# Chime_PCB.net
KiCad netlist of a schematic drawn in EAGLE
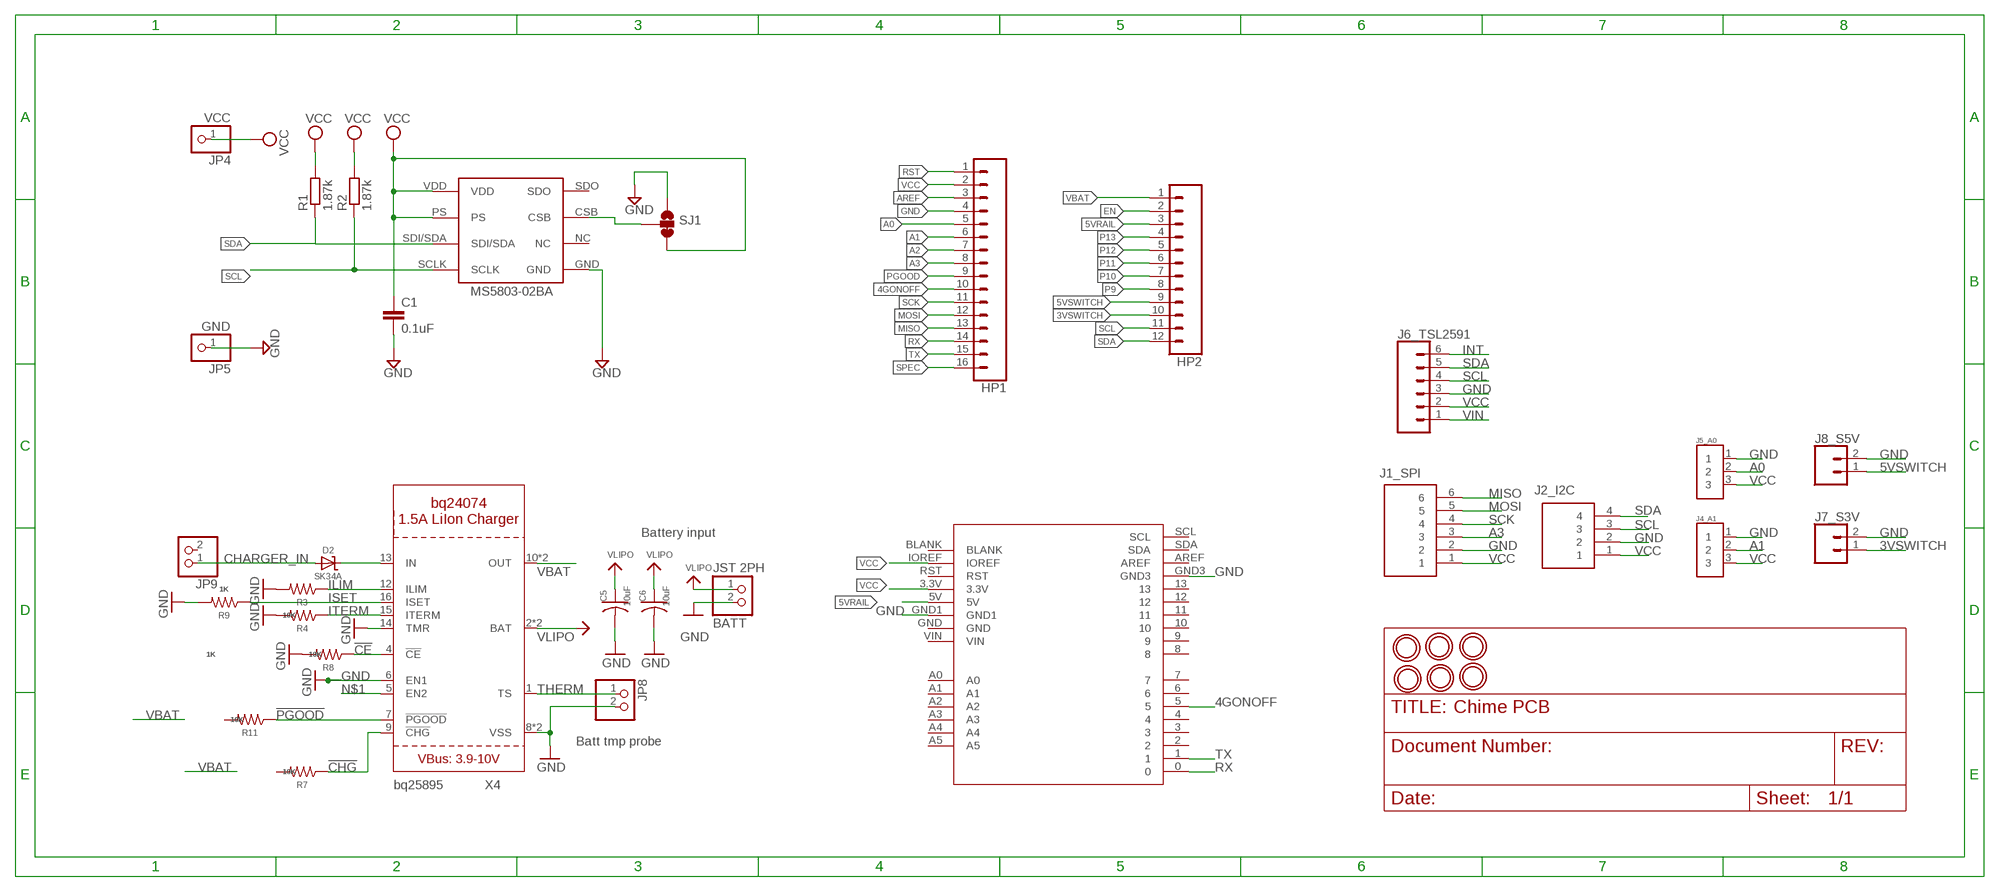
[diagram p0: schematic, sheet 1]

(export (version "E")
  (design (tool "Eeschema 10.0.6"))
  (components
    (comp (ref "BATT")
      (value "JST 2PH")
      (footprint "eagle-import:JST-PH-2-SMT-RA")
      (libsource (lib "eagle-import") (part "JST_2PIN-SMT-RA"))
    )
    (comp (ref "C1")
      (value "0.1uF")
      (footprint "eagle-import:C0805")
      (libsource (lib "eagle-import") (part "C-EUC0805"))
    )
    (comp (ref "C5")
      (value "10uF")
      (footprint "eagle-import:C0805K")
      (libsource (lib "eagle-import") (part "C-USC0805K"))
    )
    (comp (ref "C6")
      (value "10uF")
      (footprint "eagle-import:C0805K")
      (libsource (lib "eagle-import") (part "C-USC0805K"))
    )
    (comp (ref "D2")
      (value "SK34A")
      (footprint "eagle-import:SMADIODE")
      (libsource (lib "eagle-import") (part "DIODE-SCHOTTKYSMA"))
    )
    (comp (ref "HP1")
      (value "CONN_16")
      (footprint "eagle-import:1X16")
      (libsource (lib "eagle-import") (part "CONN_16"))
    )
    (comp (ref "HP2")
      (value "CONN_12")
      (footprint "eagle-import:1X12")
      (libsource (lib "eagle-import") (part "CONN_12"))
    )
    (comp (ref "J1_SPI")
      (value "1725698")
      (footprint "eagle-import:1725698")
      (fields (field (name "MOUSER_PART_NUMBER") "651-1725698"))
      (libsource (lib "eagle-import") (part "1725698"))
    )
    (comp (ref "J2_I2C")
      (value "1725672")
      (footprint "eagle-import:1725672")
      (fields (field (name "MOUSER_PART_NUMBER") "651-1725672"))
      (libsource (lib "eagle-import") (part "1725672"))
    )
    (comp (ref "J4_A1")
      (value "282834-3")
      (footprint "eagle-import:TE_282834-3")
      (fields (field (name "MF") "TE Connectivity"))
      (libsource (lib "eagle-import") (part "282834-3"))
    )
    (comp (ref "J5_A0")
      (value "282834-3")
      (footprint "eagle-import:TE_282834-3")
      (fields (field (name "MF") "TE Connectivity"))
      (libsource (lib "eagle-import") (part "282834-3"))
    )
    (comp (ref "J6_TSL2591")
      (value "CONN_06LOCK")
      (footprint "eagle-import:1X06_LOCK")
      (libsource (lib "eagle-import") (part "CONN_06LOCK"))
    )
    (comp (ref "J7_S3V")
      (value "CONN_02")
      (footprint "eagle-import:1X02")
      (libsource (lib "eagle-import") (part "CONN_02"))
    )
    (comp (ref "J8_S5V")
      (value "CONN_02")
      (footprint "eagle-import:1X02")
      (libsource (lib "eagle-import") (part "CONN_02"))
    )
    (comp (ref "JP4")
      (value "VCC")
      (footprint "eagle-import:1X01")
      (libsource (lib "eagle-import") (part "PINHD-1X1"))
    )
    (comp (ref "JP5")
      (value "GND")
      (footprint "eagle-import:1X01")
      (libsource (lib "eagle-import") (part "PINHD-1X1"))
    )
    (comp (ref "JP8")
      (value "PINHD-1X2")
      (footprint "eagle-import:1X02")
      (libsource (lib "eagle-import") (part "PINHD-1X2"))
    )
    (comp (ref "JP9")
      (value "PINHD-1X2")
      (footprint "eagle-import:1X02")
      (libsource (lib "eagle-import") (part "PINHD-1X2"))
    )
    (comp (ref "R1")
      (value "1.87k")
      (footprint "eagle-import:R0805")
      (libsource (lib "eagle-import") (part "R-EU_R0805"))
    )
    (comp (ref "R2")
      (value "1.87k")
      (footprint "eagle-import:R0805")
      (libsource (lib "eagle-import") (part "R-EU_R0805"))
    )
    (comp (ref "R3")
      (value "1K")
      (footprint "eagle-import:M0805")
      (libsource (lib "eagle-import") (part "R-US_M0805"))
    )
    (comp (ref "R4")
      (value "10K")
      (footprint "eagle-import:M0805")
      (libsource (lib "eagle-import") (part "R-US_M0805"))
    )
    (comp (ref "R7")
      (value "10K")
      (footprint "eagle-import:M0805")
      (libsource (lib "eagle-import") (part "R-US_M0805"))
    )
    (comp (ref "R8")
      (value "10K")
      (footprint "eagle-import:M0805")
      (libsource (lib "eagle-import") (part "R-US_M0805"))
    )
    (comp (ref "R9")
      (value "1K")
      (footprint "eagle-import:M0805")
      (libsource (lib "eagle-import") (part "R-US_M0805"))
    )
    (comp (ref "R11")
      (value "10K")
      (footprint "eagle-import:M0805")
      (libsource (lib "eagle-import") (part "R-US_M0805"))
    )
    (comp (ref "SJ1")
      (value "JUMPER-SMT_3_1-NC_TRACE_SILK")
      (footprint "eagle-import:SMT-JUMPER_3_1-NC_TRACE_SILK")
      (libsource (lib "eagle-import") (part "JUMPER-SMT_3_1-NC_TRACE_SILK"))
    )
    (comp (ref "U$1")
      (value "LTE_BOARD")
      (footprint "eagle-import:LTE_BOARD_FOOTPRINT")
      (libsource (lib "eagle-import") (part "LTE_BOARD"))
    )
    (comp (ref "U$2")
      (value "MOUNTINGHOLE2.5")
      (footprint "eagle-import:MOUNTINGHOLE_2.5_PLATED")
      (libsource (lib "eagle-import") (part "MOUNTINGHOLE2.5"))
    )
    (comp (ref "U$3")
      (value "MOUNTINGHOLE2.5")
      (footprint "eagle-import:MOUNTINGHOLE_2.5_PLATED")
      (libsource (lib "eagle-import") (part "MOUNTINGHOLE2.5"))
    )
    (comp (ref "U$4")
      (value "MOUNTINGHOLE2.5")
      (footprint "eagle-import:MOUNTINGHOLE_2.5_PLATED")
      (libsource (lib "eagle-import") (part "MOUNTINGHOLE2.5"))
    )
    (comp (ref "U$5")
      (value "MOUNTINGHOLE2.5")
      (footprint "eagle-import:MOUNTINGHOLE_2.5_PLATED")
      (libsource (lib "eagle-import") (part "MOUNTINGHOLE2.5"))
    )
    (comp (ref "U$17")
      (value "MOUNTINGHOLE2.5")
      (footprint "eagle-import:MOUNTINGHOLE_2.5_PLATED")
      (libsource (lib "eagle-import") (part "MOUNTINGHOLE2.5"))
    )
    (comp (ref "U$19")
      (value "MOUNTINGHOLE2.5")
      (footprint "eagle-import:MOUNTINGHOLE_2.5_PLATED")
      (libsource (lib "eagle-import") (part "MOUNTINGHOLE2.5"))
    )
    (comp (ref "U1")
      (value "MS5803-02BA")
      (footprint "eagle-import:MS5803-02BA")
      (libsource (lib "eagle-import") (part "MS5803-02BA"))
    )
    (comp (ref "X4")
      (value "BQ24074")
      (footprint "eagle-import:QFN16_3MM")
      (libsource (lib "eagle-import") (part "BQ24074"))
    )
  )
  (nets
    (net (code "1") (name "/CHARGER_IN") (class "Default")
      (node (ref "D2") (pin "A") (pinfunction "A_A") (pintype "passive"))
      (node (ref "JP9") (pin "1") (pinfunction "1_1") (pintype "passive"))
    )
    (net (code "2") (name "/ILIM") (class "Default")
      (node (ref "R3") (pin "1") (pinfunction "1_1") (pintype "passive"))
      (node (ref "X4") (pin "12") (pinfunction "ILIM_12") (pintype "input"))
    )
    (net (code "3") (name "/INT") (class "Default")
      (node (ref "J6_TSL2591") (pin "6") (pinfunction "6_6") (pintype "passive"))
    )
    (net (code "4") (name "/ISET") (class "Default")
      (node (ref "R9") (pin "1") (pinfunction "1_1") (pintype "passive"))
      (node (ref "X4") (pin "16") (pinfunction "ISET_16") (pintype "input"))
    )
    (net (code "5") (name "/ITERM") (class "Default")
      (node (ref "R4") (pin "1") (pinfunction "1_1") (pintype "passive"))
      (node (ref "X4") (pin "15") (pinfunction "ITERM_15") (pintype "input"))
    )
    (net (code "6") (name "/N$1") (class "Default")
      (node (ref "X4") (pin "5") (pinfunction "EN2_5") (pintype "input"))
    )
    (net (code "7") (name "/THERM") (class "Default")
      (node (ref "JP8") (pin "1") (pinfunction "1_1") (pintype "passive"))
      (node (ref "X4") (pin "1") (pinfunction "TS_1") (pintype "input"))
    )
    (net (code "8") (name "/VIN") (class "Default")
      (node (ref "J6_TSL2591") (pin "1") (pinfunction "1_1") (pintype "passive"))
    )
    (net (code "9") (name "/~{CE}") (class "Default")
      (node (ref "R8") (pin "1") (pinfunction "1_1") (pintype "passive"))
      (node (ref "X4") (pin "4") (pinfunction "~{CE}_4") (pintype "input"))
    )
    (net (code "10") (name "/~{CHG}") (class "Default")
      (node (ref "R7") (pin "1") (pinfunction "1_1") (pintype "passive"))
      (node (ref "X4") (pin "9") (pinfunction "~{CHG}_9") (pintype "output"))
    )
    (net (code "11") (name "/~{PGOOD}") (class "Default")
      (node (ref "R11") (pin "1") (pinfunction "1_1") (pintype "passive"))
      (node (ref "X4") (pin "7") (pinfunction "~{PGOOD}_7") (pintype "output"))
    )
    (net (code "12") (name "3VSWITCH") (class "Default")
      (node (ref "HP2") (pin "10") (pinfunction "10_10") (pintype "passive"))
      (node (ref "J7_S3V") (pin "1") (pinfunction "1_1") (pintype "passive"))
    )
    (net (code "13") (name "4GONOFF") (class "Default")
      (node (ref "HP1") (pin "10") (pinfunction "10_10") (pintype "passive"))
      (node (ref "U$1") (pin "5") (pinfunction "5_5") (pintype "bidirectional"))
    )
    (net (code "14") (name "5VRAIL") (class "Default")
      (node (ref "HP2") (pin "3") (pinfunction "3_3") (pintype "passive"))
      (node (ref "U$1") (pin "5V") (pinfunction "5V_5V") (pintype "bidirectional"))
    )
    (net (code "15") (name "5VSWITCH") (class "Default")
      (node (ref "HP2") (pin "9") (pinfunction "9_9") (pintype "passive"))
      (node (ref "J8_S5V") (pin "1") (pinfunction "1_1") (pintype "passive"))
    )
    (net (code "16") (name "A0") (class "Default")
      (node (ref "HP1") (pin "5") (pinfunction "5_5") (pintype "passive"))
      (node (ref "J5_A0") (pin "2") (pinfunction "2_2") (pintype "passive"))
    )
    (net (code "17") (name "A1") (class "Default")
      (node (ref "HP1") (pin "6") (pinfunction "6_6") (pintype "passive"))
      (node (ref "J4_A1") (pin "2") (pinfunction "2_2") (pintype "passive"))
    )
    (net (code "18") (name "A2") (class "Default")
      (node (ref "HP1") (pin "7") (pinfunction "7_7") (pintype "passive"))
    )
    (net (code "19") (name "A3") (class "Default")
      (node (ref "HP1") (pin "8") (pinfunction "8_8") (pintype "passive"))
      (node (ref "J1_SPI") (pin "3") (pinfunction "3_3") (pintype "bidirectional"))
    )
    (net (code "20") (name "AREF") (class "Default")
      (node (ref "HP1") (pin "3") (pinfunction "3_3") (pintype "passive"))
    )
    (net (code "21") (name "EN") (class "Default")
      (node (ref "HP2") (pin "2") (pinfunction "2_2") (pintype "passive"))
    )
    (net (code "22") (name "GND") (class "Default")
      (node (ref "BATT") (pin "2") (pinfunction "1_2") (pintype "passive"))
      (node (ref "C1") (pin "2") (pinfunction "2_2") (pintype "passive"))
      (node (ref "C5") (pin "2") (pinfunction "2_2") (pintype "passive"))
      (node (ref "C6") (pin "2") (pinfunction "2_2") (pintype "passive"))
      (node (ref "HP1") (pin "4") (pinfunction "4_4") (pintype "passive"))
      (node (ref "J1_SPI") (pin "2") (pinfunction "2_2") (pintype "bidirectional"))
      (node (ref "J2_I2C") (pin "2") (pinfunction "2_2") (pintype "bidirectional"))
      (node (ref "J4_A1") (pin "1") (pinfunction "1_1") (pintype "passive"))
      (node (ref "J5_A0") (pin "1") (pinfunction "1_1") (pintype "passive"))
      (node (ref "J6_TSL2591") (pin "3") (pinfunction "3_3") (pintype "passive"))
      (node (ref "J7_S3V") (pin "2") (pinfunction "2_2") (pintype "passive"))
      (node (ref "J8_S5V") (pin "2") (pinfunction "2_2") (pintype "passive"))
      (node (ref "JP5") (pin "1") (pinfunction "1_1") (pintype "passive"))
      (node (ref "JP8") (pin "2") (pinfunction "2_2") (pintype "passive"))
      (node (ref "R3") (pin "2") (pinfunction "2_2") (pintype "passive"))
      (node (ref "R4") (pin "2") (pinfunction "2_2") (pintype "passive"))
      (node (ref "R8") (pin "2") (pinfunction "2_2") (pintype "passive"))
      (node (ref "R9") (pin "2") (pinfunction "2_2") (pintype "passive"))
      (node (ref "SJ1") (pin "1") (pinfunction "1_1") (pintype "passive"))
      (node (ref "U$1") (pin "GND1") (pinfunction "GND1_GND1") (pintype "bidirectional"))
      (node (ref "U$1") (pin "GND3") (pinfunction "GND3_GND3") (pintype "bidirectional"))
      (node (ref "U1") (pin "GND") (pinfunction "GND_GND") (pintype "bidirectional"))
      (node (ref "X4") (pin "14") (pinfunction "TMR_14") (pintype "input"))
      (node (ref "X4") (pin "6") (pinfunction "EN1_6") (pintype "input"))
      (node (ref "X4") (pin "8") (pinfunction "VSS_8") (pintype "power_in"))
      (node (ref "X4") (pin "THERMAL") (pinfunction "VSS_THERMAL") (pintype "power_in"))
    )
    (net (code "23") (name "MISO") (class "Default")
      (node (ref "HP1") (pin "13") (pinfunction "13_13") (pintype "passive"))
      (node (ref "J1_SPI") (pin "6") (pinfunction "6_6") (pintype "bidirectional"))
    )
    (net (code "24") (name "MOSI") (class "Default")
      (node (ref "HP1") (pin "12") (pinfunction "12_12") (pintype "passive"))
      (node (ref "J1_SPI") (pin "5") (pinfunction "5_5") (pintype "bidirectional"))
    )
    (net (code "25") (name "Net-(SJ1-Pad2)") (class "Default")
      (node (ref "SJ1") (pin "2") (pinfunction "2_2") (pintype "passive"))
      (node (ref "U1") (pin "CSB") (pinfunction "CSB_CSB") (pintype "bidirectional"))
    )
    (net (code "26") (name "Net-(X4-IN)") (class "Default")
      (node (ref "D2") (pin "C") (pinfunction "C_C") (pintype "passive"))
      (node (ref "X4") (pin "13") (pinfunction "IN_13") (pintype "power_in"))
    )
    (net (code "27") (name "P9") (class "Default")
      (node (ref "HP2") (pin "8") (pinfunction "8_8") (pintype "passive"))
    )
    (net (code "28") (name "P10") (class "Default")
      (node (ref "HP2") (pin "7") (pinfunction "7_7") (pintype "passive"))
    )
    (net (code "29") (name "P11") (class "Default")
      (node (ref "HP2") (pin "6") (pinfunction "6_6") (pintype "passive"))
    )
    (net (code "30") (name "P12") (class "Default")
      (node (ref "HP2") (pin "5") (pinfunction "5_5") (pintype "passive"))
    )
    (net (code "31") (name "P13") (class "Default")
      (node (ref "HP2") (pin "4") (pinfunction "4_4") (pintype "passive"))
    )
    (net (code "32") (name "PGOOD") (class "Default")
      (node (ref "HP1") (pin "9") (pinfunction "9_9") (pintype "passive"))
    )
    (net (code "33") (name "RST") (class "Default")
      (node (ref "HP1") (pin "1") (pinfunction "1_1") (pintype "passive"))
    )
    (net (code "34") (name "RX") (class "Default")
      (node (ref "HP1") (pin "14") (pinfunction "14_14") (pintype "passive"))
      (node (ref "U$1") (pin "0") (pinfunction "0_0") (pintype "bidirectional"))
    )
    (net (code "35") (name "SCK") (class "Default")
      (node (ref "HP1") (pin "11") (pinfunction "11_11") (pintype "passive"))
      (node (ref "J1_SPI") (pin "4") (pinfunction "4_4") (pintype "bidirectional"))
    )
    (net (code "36") (name "SCL") (class "Default")
      (node (ref "HP2") (pin "11") (pinfunction "11_11") (pintype "passive"))
      (node (ref "J2_I2C") (pin "3") (pinfunction "3_3") (pintype "bidirectional"))
      (node (ref "J6_TSL2591") (pin "4") (pinfunction "4_4") (pintype "passive"))
      (node (ref "R2") (pin "1") (pinfunction "1_1") (pintype "passive"))
      (node (ref "U1") (pin "SCLK") (pinfunction "SCLK_SCLK") (pintype "bidirectional"))
    )
    (net (code "37") (name "SDA") (class "Default")
      (node (ref "HP2") (pin "12") (pinfunction "12_12") (pintype "passive"))
      (node (ref "J2_I2C") (pin "4") (pinfunction "4_4") (pintype "bidirectional"))
      (node (ref "J6_TSL2591") (pin "5") (pinfunction "5_5") (pintype "passive"))
      (node (ref "R1") (pin "1") (pinfunction "1_1") (pintype "passive"))
      (node (ref "U1") (pin "SDI/SDA") (pinfunction "SDI/SDA_SDI/SDA") (pintype "bidirectional"))
    )
    (net (code "38") (name "SPEC") (class "Default")
      (node (ref "HP1") (pin "16") (pinfunction "16_16") (pintype "passive"))
    )
    (net (code "39") (name "TX") (class "Default")
      (node (ref "HP1") (pin "15") (pinfunction "15_15") (pintype "passive"))
      (node (ref "U$1") (pin "1") (pinfunction "1_1") (pintype "bidirectional"))
    )
    (net (code "40") (name "VBAT") (class "Default")
      (node (ref "HP2") (pin "1") (pinfunction "1_1") (pintype "passive"))
      (node (ref "X4") (pin "10") (pinfunction "OUT_10") (pintype "output"))
      (node (ref "X4") (pin "11") (pinfunction "OUT_11") (pintype "output"))
    )
    (net (code "41") (name "VCC") (class "Default")
      (node (ref "C1") (pin "1") (pinfunction "1_1") (pintype "passive"))
      (node (ref "HP1") (pin "2") (pinfunction "2_2") (pintype "passive"))
      (node (ref "J1_SPI") (pin "1") (pinfunction "1_1") (pintype "bidirectional"))
      (node (ref "J2_I2C") (pin "1") (pinfunction "1_1") (pintype "bidirectional"))
      (node (ref "J4_A1") (pin "3") (pinfunction "3_3") (pintype "passive"))
      (node (ref "J5_A0") (pin "3") (pinfunction "3_3") (pintype "passive"))
      (node (ref "J6_TSL2591") (pin "2") (pinfunction "2_2") (pintype "passive"))
      (node (ref "JP4") (pin "1") (pinfunction "1_1") (pintype "passive"))
      (node (ref "R1") (pin "2") (pinfunction "2_2") (pintype "passive"))
      (node (ref "R2") (pin "2") (pinfunction "2_2") (pintype "passive"))
      (node (ref "SJ1") (pin "3") (pinfunction "3_3") (pintype "passive"))
      (node (ref "U$1") (pin "3.3V") (pinfunction "3.3V_3.3V") (pintype "bidirectional"))
      (node (ref "U$1") (pin "IOREF") (pinfunction "IOREF_IOREF") (pintype "bidirectional"))
      (node (ref "U1") (pin "PS") (pinfunction "PS_PS") (pintype "bidirectional"))
      (node (ref "U1") (pin "VDD") (pinfunction "VDD_VDD") (pintype "bidirectional"))
    )
    (net (code "42") (name "VLIPO") (class "Default")
      (node (ref "BATT") (pin "1") (pinfunction "2_1") (pintype "passive"))
      (node (ref "C5") (pin "1") (pinfunction "1_1") (pintype "passive"))
      (node (ref "C6") (pin "1") (pinfunction "1_1") (pintype "passive"))
      (node (ref "X4") (pin "2") (pinfunction "BAT_2") (pintype "input"))
      (node (ref "X4") (pin "3") (pinfunction "BAT_3") (pintype "input"))
    )
    (net (code "43") (name "unconnected-(JP9-Pad2)") (class "Default")
      (node (ref "JP9") (pin "2") (pinfunction "2_2") (pintype "passive"))
    )
    (net (code "44") (name "unconnected-(R7-Pad2)") (class "Default")
      (node (ref "R7") (pin "2") (pinfunction "2_2") (pintype "passive"))
    )
    (net (code "45") (name "unconnected-(R11-Pad2)") (class "Default")
      (node (ref "R11") (pin "2") (pinfunction "2_2") (pintype "passive"))
    )
    (net (code "46") (name "unconnected-(U$1-Pad2)") (class "Default")
      (node (ref "U$1") (pin "2") (pinfunction "2_2") (pintype "bidirectional"))
    )
    (net (code "47") (name "unconnected-(U$1-Pad3)") (class "Default")
      (node (ref "U$1") (pin "3") (pinfunction "3_3") (pintype "bidirectional"))
    )
    (net (code "48") (name "unconnected-(U$1-Pad4)") (class "Default")
      (node (ref "U$1") (pin "4") (pinfunction "4_4") (pintype "bidirectional"))
    )
    (net (code "49") (name "unconnected-(U$1-Pad6)") (class "Default")
      (node (ref "U$1") (pin "6") (pinfunction "6_6") (pintype "bidirectional"))
    )
    (net (code "50") (name "unconnected-(U$1-Pad7)") (class "Default")
      (node (ref "U$1") (pin "7") (pinfunction "7_7") (pintype "bidirectional"))
    )
    (net (code "51") (name "unconnected-(U$1-Pad8)") (class "Default")
      (node (ref "U$1") (pin "8") (pinfunction "8_8") (pintype "bidirectional"))
    )
    (net (code "52") (name "unconnected-(U$1-Pad9)") (class "Default")
      (node (ref "U$1") (pin "9") (pinfunction "9_9") (pintype "bidirectional"))
    )
    (net (code "53") (name "unconnected-(U$1-Pad10)") (class "Default")
      (node (ref "U$1") (pin "10") (pinfunction "10_10") (pintype "bidirectional"))
    )
    (net (code "54") (name "unconnected-(U$1-Pad11)") (class "Default")
      (node (ref "U$1") (pin "11") (pinfunction "11_11") (pintype "bidirectional"))
    )
    (net (code "55") (name "unconnected-(U$1-Pad12)") (class "Default")
      (node (ref "U$1") (pin "12") (pinfunction "12_12") (pintype "bidirectional"))
    )
    (net (code "56") (name "unconnected-(U$1-Pad13)") (class "Default")
      (node (ref "U$1") (pin "13") (pinfunction "13_13") (pintype "bidirectional"))
    )
    (net (code "57") (name "unconnected-(U$1-PadA0)") (class "Default")
      (node (ref "U$1") (pin "A0") (pinfunction "A0_A0") (pintype "bidirectional"))
    )
    (net (code "58") (name "unconnected-(U$1-PadA1)") (class "Default")
      (node (ref "U$1") (pin "A1") (pinfunction "A1_A1") (pintype "bidirectional"))
    )
    (net (code "59") (name "unconnected-(U$1-PadA2)") (class "Default")
      (node (ref "U$1") (pin "A2") (pinfunction "A2_A2") (pintype "bidirectional"))
    )
    (net (code "60") (name "unconnected-(U$1-PadA3)") (class "Default")
      (node (ref "U$1") (pin "A3") (pinfunction "A3_A3") (pintype "bidirectional"))
    )
    (net (code "61") (name "unconnected-(U$1-PadA4)") (class "Default")
      (node (ref "U$1") (pin "A4") (pinfunction "A4_A4") (pintype "bidirectional"))
    )
    (net (code "62") (name "unconnected-(U$1-PadA5)") (class "Default")
      (node (ref "U$1") (pin "A5") (pinfunction "A5_A5") (pintype "bidirectional"))
    )
    (net (code "63") (name "unconnected-(U$1-PadAREF)") (class "Default")
      (node (ref "U$1") (pin "AREF") (pinfunction "AREF_AREF") (pintype "bidirectional"))
    )
    (net (code "64") (name "unconnected-(U$1-PadBLANK)") (class "Default")
      (node (ref "U$1") (pin "BLANK") (pinfunction "BLANK_BLANK") (pintype "bidirectional"))
    )
    (net (code "65") (name "unconnected-(U$1-PadGND)") (class "Default")
      (node (ref "U$1") (pin "GND") (pinfunction "GND_GND") (pintype "bidirectional"))
    )
    (net (code "66") (name "unconnected-(U$1-PadRST)") (class "Default")
      (node (ref "U$1") (pin "RST") (pinfunction "RST_RST") (pintype "bidirectional"))
    )
    (net (code "67") (name "unconnected-(U$1-PadSCL)") (class "Default")
      (node (ref "U$1") (pin "SCL") (pinfunction "SCL_SCL") (pintype "bidirectional"))
    )
    (net (code "68") (name "unconnected-(U$1-PadSDA)") (class "Default")
      (node (ref "U$1") (pin "SDA") (pinfunction "SDA_SDA") (pintype "bidirectional"))
    )
    (net (code "69") (name "unconnected-(U$1-PadVIN)") (class "Default")
      (node (ref "U$1") (pin "VIN") (pinfunction "VIN_VIN") (pintype "bidirectional"))
    )
    (net (code "70") (name "unconnected-(U1-PadNC)") (class "Default")
      (node (ref "U1") (pin "NC") (pinfunction "NC_NC") (pintype "bidirectional"))
    )
    (net (code "71") (name "unconnected-(U1-PadSDO)") (class "Default")
      (node (ref "U1") (pin "SDO") (pinfunction "SDO_SDO") (pintype "bidirectional"))
    )
  )
)
